# pinouts.net
KiCad netlist of a schematic drawn in EAGLE
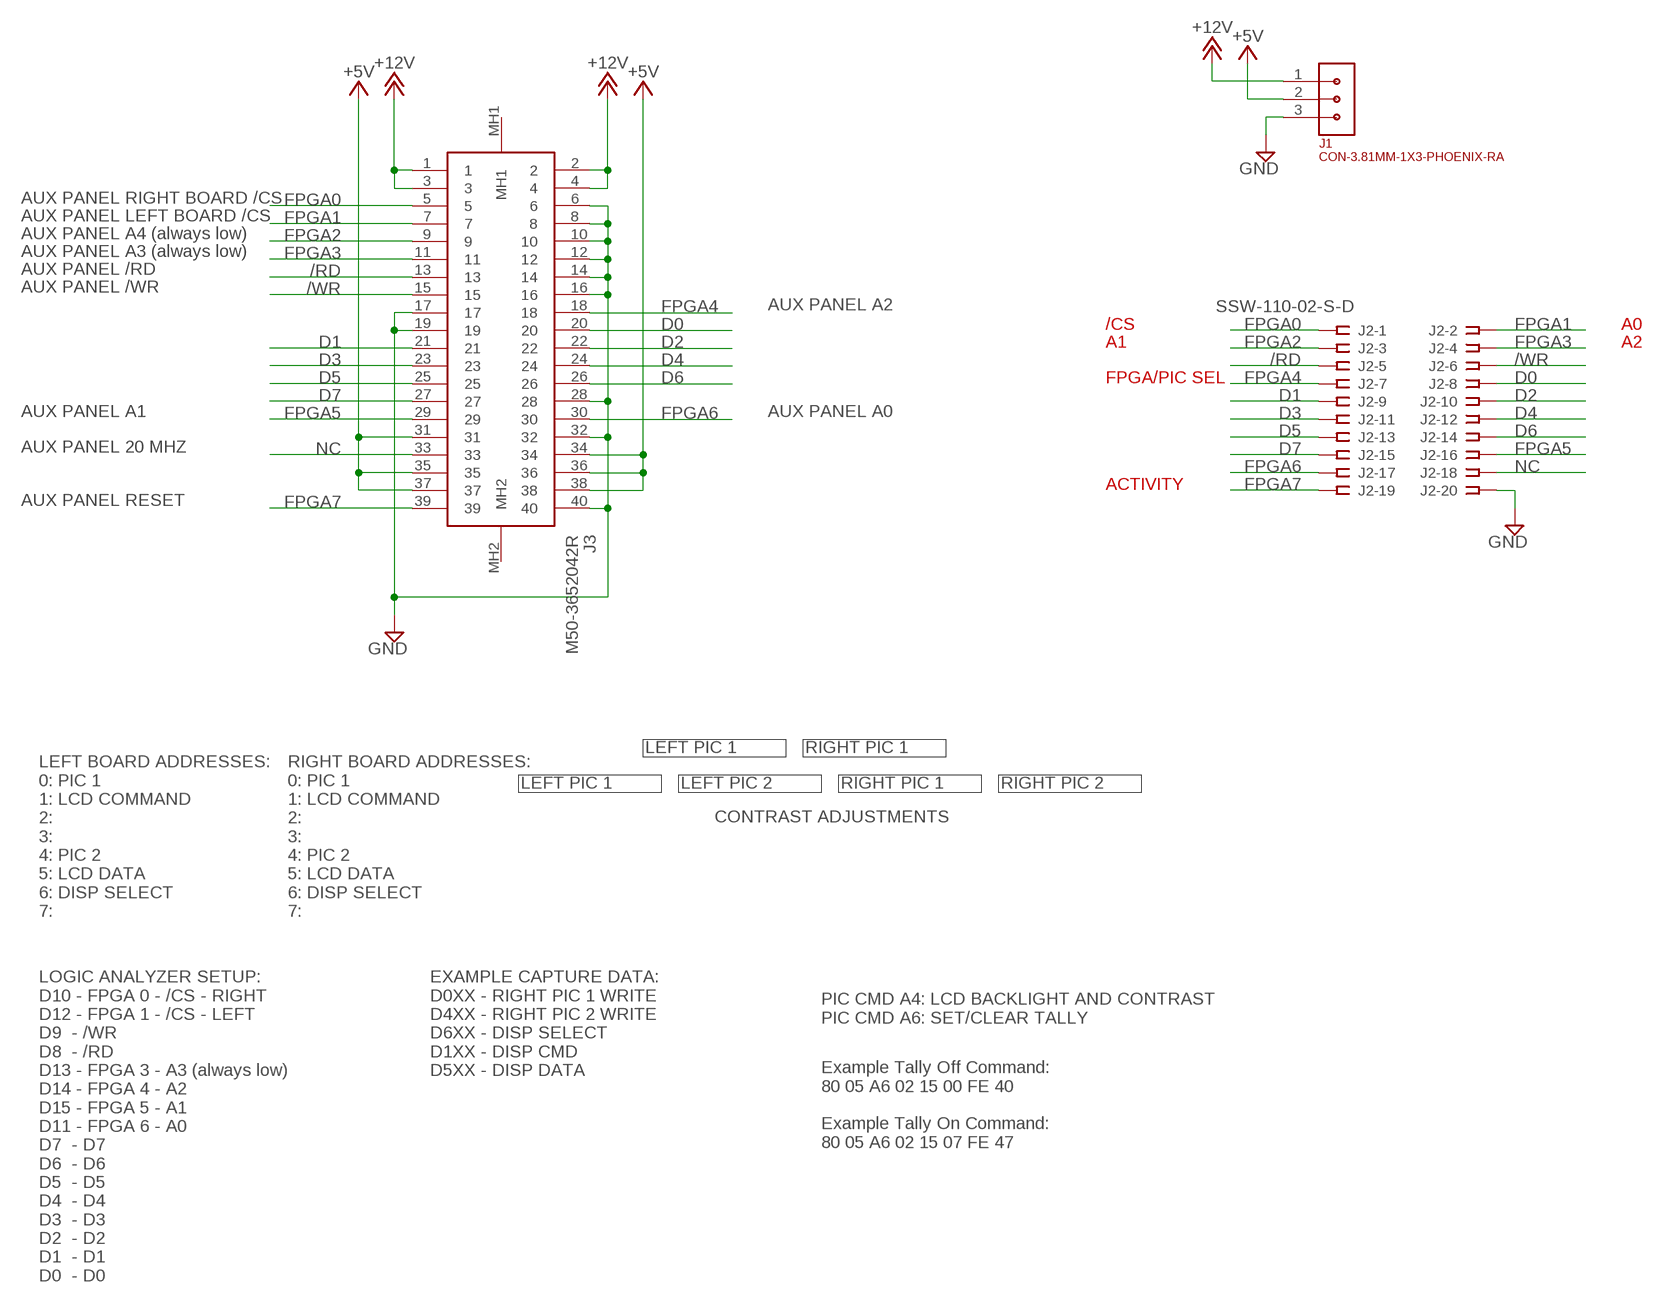
[diagram p0: schematic, sheet 1]

(export (version "E")
  (design (tool "Eeschema 10.0.6"))
  (components
    (comp (ref "J1")
      (value "CON-3.81MM-1X3-PHOENIX-RA")
      (footprint "eagle-import:CON-PHOENIX-3.81-1X3-RA")
      (libsource (lib "eagle-import") (part "CON-3.81MM-1X3-PHOENIX-RA"))
    )
    (comp (ref "J2")
      (value "SSW-110-02-S-D")
      (footprint "eagle-import:SSW-110-02-S-D")
      (libsource (lib "eagle-import") (part "SSW-110-02-S-D"))
    )
    (comp (ref "J3")
      (value "M50-3652042R")
      (footprint "eagle-import:M503652042R")
      (fields (field (name "MOUSER_PART_NUMBER") "855-M50-3652042R"))
      (libsource (lib "eagle-import") (part "M50-3652042R"))
    )
  )
  (nets
    (net (code "1") (name "+5V") (class "Default")
      (node (ref "J1") (pin "2") (pinfunction "2_2") (pintype "bidirectional"))
      (node (ref "J3") (pin "31") (pinfunction "31_31") (pintype "bidirectional"))
      (node (ref "J3") (pin "34") (pinfunction "34_34") (pintype "bidirectional"))
      (node (ref "J3") (pin "35") (pinfunction "35_35") (pintype "bidirectional"))
      (node (ref "J3") (pin "36") (pinfunction "36_36") (pintype "bidirectional"))
      (node (ref "J3") (pin "37") (pinfunction "37_37") (pintype "bidirectional"))
      (node (ref "J3") (pin "38") (pinfunction "38_38") (pintype "bidirectional"))
    )
    (net (code "2") (name "+12V") (class "Default")
      (node (ref "J1") (pin "1") (pinfunction "1_1") (pintype "bidirectional"))
      (node (ref "J3") (pin "1") (pinfunction "1_1") (pintype "bidirectional"))
      (node (ref "J3") (pin "2") (pinfunction "2_2") (pintype "bidirectional"))
      (node (ref "J3") (pin "3") (pinfunction "3_3") (pintype "bidirectional"))
      (node (ref "J3") (pin "4") (pinfunction "4_4") (pintype "bidirectional"))
    )
    (net (code "3") (name "/D0") (class "Default")
      (node (ref "J2") (pin "8") (pinfunction "1_8") (pintype "passive"))
      (node (ref "J3") (pin "20") (pinfunction "20_20") (pintype "bidirectional"))
    )
    (net (code "4") (name "/D1") (class "Default")
      (node (ref "J2") (pin "9") (pinfunction "1_9") (pintype "passive"))
      (node (ref "J3") (pin "21") (pinfunction "21_21") (pintype "bidirectional"))
    )
    (net (code "5") (name "/D2") (class "Default")
      (node (ref "J2") (pin "10") (pinfunction "1_10") (pintype "passive"))
      (node (ref "J3") (pin "22") (pinfunction "22_22") (pintype "bidirectional"))
    )
    (net (code "6") (name "/D3") (class "Default")
      (node (ref "J2") (pin "11") (pinfunction "1_11") (pintype "passive"))
      (node (ref "J3") (pin "23") (pinfunction "23_23") (pintype "bidirectional"))
    )
    (net (code "7") (name "/D4") (class "Default")
      (node (ref "J2") (pin "12") (pinfunction "1_12") (pintype "passive"))
      (node (ref "J3") (pin "24") (pinfunction "24_24") (pintype "bidirectional"))
    )
    (net (code "8") (name "/D5") (class "Default")
      (node (ref "J2") (pin "13") (pinfunction "1_13") (pintype "passive"))
      (node (ref "J3") (pin "25") (pinfunction "25_25") (pintype "bidirectional"))
    )
    (net (code "9") (name "/D6") (class "Default")
      (node (ref "J2") (pin "14") (pinfunction "1_14") (pintype "passive"))
      (node (ref "J3") (pin "26") (pinfunction "26_26") (pintype "bidirectional"))
    )
    (net (code "10") (name "/D7") (class "Default")
      (node (ref "J2") (pin "15") (pinfunction "1_15") (pintype "passive"))
      (node (ref "J3") (pin "27") (pinfunction "27_27") (pintype "bidirectional"))
    )
    (net (code "11") (name "/FPGA0") (class "Default")
      (node (ref "J2") (pin "1") (pinfunction "1_1") (pintype "passive"))
      (node (ref "J3") (pin "5") (pinfunction "5_5") (pintype "bidirectional"))
    )
    (net (code "12") (name "/FPGA1") (class "Default")
      (node (ref "J2") (pin "2") (pinfunction "1_2") (pintype "passive"))
      (node (ref "J3") (pin "7") (pinfunction "7_7") (pintype "bidirectional"))
    )
    (net (code "13") (name "/FPGA2") (class "Default")
      (node (ref "J2") (pin "3") (pinfunction "1_3") (pintype "passive"))
      (node (ref "J3") (pin "9") (pinfunction "9_9") (pintype "bidirectional"))
    )
    (net (code "14") (name "/FPGA3") (class "Default")
      (node (ref "J2") (pin "4") (pinfunction "1_4") (pintype "passive"))
      (node (ref "J3") (pin "11") (pinfunction "11_11") (pintype "bidirectional"))
    )
    (net (code "15") (name "/FPGA4") (class "Default")
      (node (ref "J2") (pin "7") (pinfunction "1_7") (pintype "passive"))
      (node (ref "J3") (pin "18") (pinfunction "18_18") (pintype "bidirectional"))
    )
    (net (code "16") (name "/FPGA5") (class "Default")
      (node (ref "J2") (pin "16") (pinfunction "1_16") (pintype "passive"))
      (node (ref "J3") (pin "29") (pinfunction "29_29") (pintype "bidirectional"))
    )
    (net (code "17") (name "/FPGA6") (class "Default")
      (node (ref "J2") (pin "17") (pinfunction "1_17") (pintype "passive"))
      (node (ref "J3") (pin "30") (pinfunction "30_30") (pintype "bidirectional"))
    )
    (net (code "18") (name "/FPGA7") (class "Default")
      (node (ref "J2") (pin "19") (pinfunction "1_19") (pintype "passive"))
      (node (ref "J3") (pin "39") (pinfunction "39_39") (pintype "bidirectional"))
    )
    (net (code "19") (name "/NC") (class "Default")
      (node (ref "J2") (pin "18") (pinfunction "1_18") (pintype "passive"))
      (node (ref "J3") (pin "33") (pinfunction "33_33") (pintype "bidirectional"))
    )
    (net (code "20") (name "/{slash}RD") (class "Default")
      (node (ref "J2") (pin "5") (pinfunction "1_5") (pintype "passive"))
      (node (ref "J3") (pin "13") (pinfunction "13_13") (pintype "bidirectional"))
    )
    (net (code "21") (name "/{slash}WR") (class "Default")
      (node (ref "J2") (pin "6") (pinfunction "1_6") (pintype "passive"))
      (node (ref "J3") (pin "15") (pinfunction "15_15") (pintype "bidirectional"))
    )
    (net (code "22") (name "GND") (class "Default")
      (node (ref "J1") (pin "3") (pinfunction "3_3") (pintype "bidirectional"))
      (node (ref "J2") (pin "20") (pinfunction "1_20") (pintype "passive"))
      (node (ref "J3") (pin "10") (pinfunction "10_10") (pintype "bidirectional"))
      (node (ref "J3") (pin "12") (pinfunction "12_12") (pintype "bidirectional"))
      (node (ref "J3") (pin "14") (pinfunction "14_14") (pintype "bidirectional"))
      (node (ref "J3") (pin "16") (pinfunction "16_16") (pintype "bidirectional"))
      (node (ref "J3") (pin "17") (pinfunction "17_17") (pintype "bidirectional"))
      (node (ref "J3") (pin "19") (pinfunction "19_19") (pintype "bidirectional"))
      (node (ref "J3") (pin "28") (pinfunction "28_28") (pintype "bidirectional"))
      (node (ref "J3") (pin "32") (pinfunction "32_32") (pintype "bidirectional"))
      (node (ref "J3") (pin "40") (pinfunction "40_40") (pintype "bidirectional"))
      (node (ref "J3") (pin "6") (pinfunction "6_6") (pintype "bidirectional"))
      (node (ref "J3") (pin "8") (pinfunction "8_8") (pintype "bidirectional"))
    )
    (net (code "23") (name "unconnected-(J3-PadMH1)") (class "Default")
      (node (ref "J3") (pin "MH1") (pinfunction "MH1_MH1") (pintype "bidirectional"))
    )
    (net (code "24") (name "unconnected-(J3-PadMH2)") (class "Default")
      (node (ref "J3") (pin "MH2") (pinfunction "MH2_MH2") (pintype "bidirectional"))
    )
  )
)
